# Swarm-Medusa-Antenna.net
KiCad netlist of a schematic drawn in Altium Designer
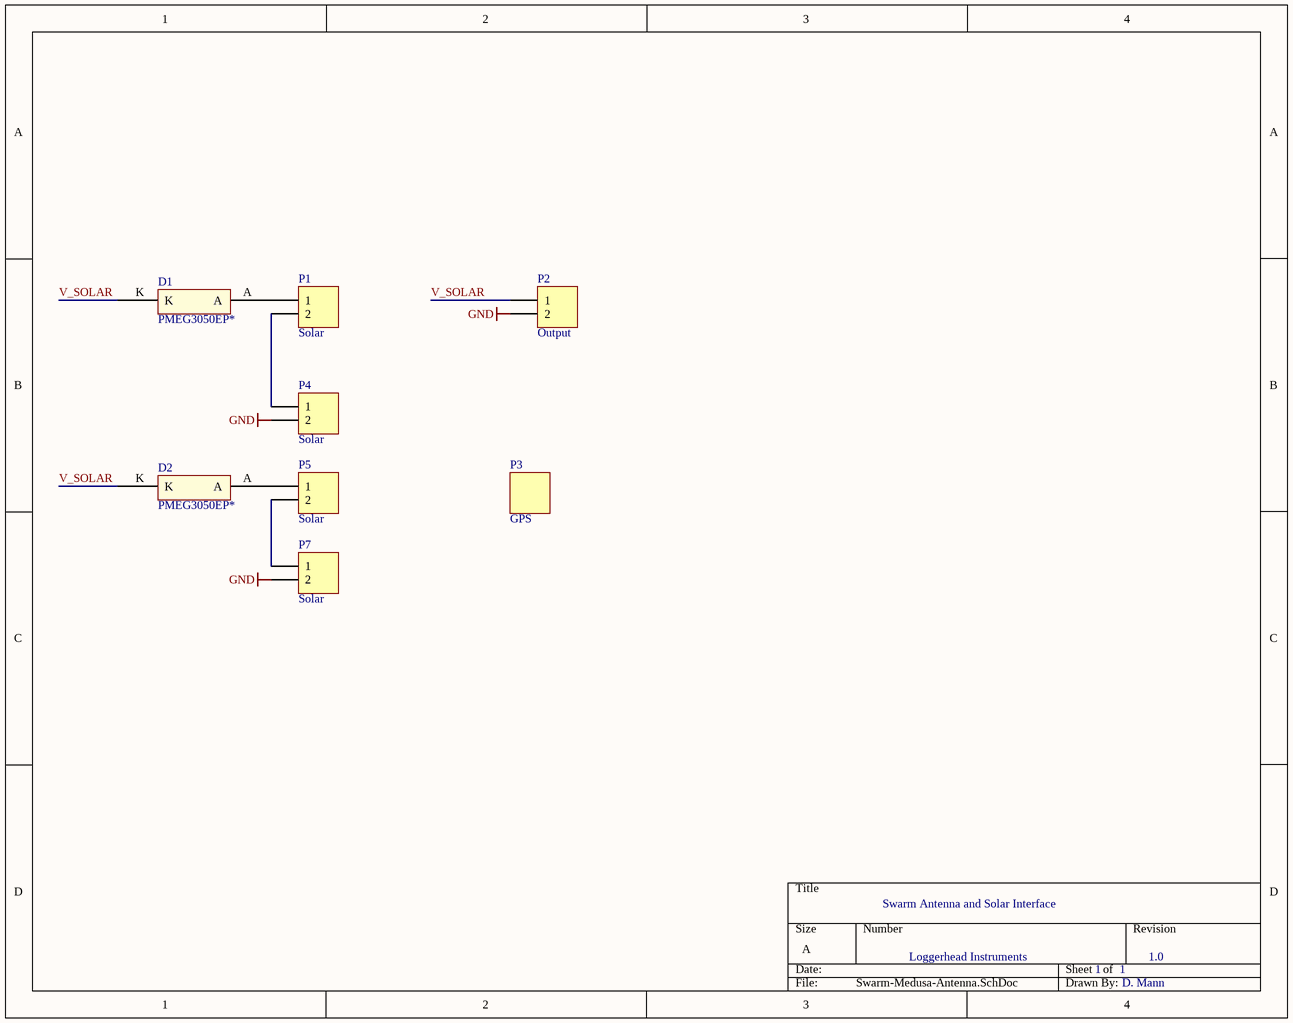
[diagram p0: Swarm-Medusa-Antenna.SchDoc]

(export (version "E")
  (design (tool "Eeschema 10.0.6"))
  (components
    (comp (ref "D1")
      (value "PMEG3050EP*")
      (footprint "Diode_PMEG3050EP")
      (libsource (lib "Loggerhead") (part "Diode_PMEG3050EP"))
    )
    (comp (ref "D2")
      (value "PMEG3050EP*")
      (footprint "Diode_PMEG3050EP")
      (libsource (lib "Loggerhead") (part "Diode_PMEG3050EP"))
    )
    (comp (ref "P1")
      (value "Solar")
      (footprint "HDR1X2")
      (description "Header, 2-Pin")
      (fields (field (name "PUBLISHER") "Altium Limited"))
      (libsource (lib "Miscellaneous Connectors") (part "Header 2"))
    )
    (comp (ref "P2")
      (value "Output")
      (footprint "HDR1X2")
      (description "Header, 2-Pin")
      (fields (field (name "PUBLISHER") "Altium Limited"))
      (libsource (lib "Miscellaneous Connectors") (part "Header 2"))
    )
    (comp (ref "P3")
      (value "GPS")
      (footprint "Iridium Antenna")
      (libsource (lib "Loggerhead") (part "Iridium Antenna"))
    )
    (comp (ref "P4")
      (value "Solar")
      (footprint "HDR1X2")
      (description "Header, 2-Pin")
      (fields (field (name "PUBLISHER") "Altium Limited"))
      (libsource (lib "Miscellaneous Connectors") (part "Header 2"))
    )
    (comp (ref "P5")
      (value "Solar")
      (footprint "HDR1X2")
      (description "Header, 2-Pin")
      (fields (field (name "PUBLISHER") "Altium Limited"))
      (libsource (lib "Miscellaneous Connectors") (part "Header 2"))
    )
    (comp (ref "P7")
      (value "Solar")
      (footprint "HDR1X2")
      (description "Header, 2-Pin")
      (fields (field (name "PUBLISHER") "Altium Limited"))
      (libsource (lib "Miscellaneous Connectors") (part "Header 2"))
    )
  )
  (nets
    (net (code "1") (name "/V_SOLAR") (class "Default")
      (node (ref "D1") (pin "K") (pinfunction "K_K") (pintype "passive"))
      (node (ref "D2") (pin "K") (pinfunction "K_K") (pintype "passive"))
      (node (ref "P2") (pin "1") (pinfunction "1_1") (pintype "passive"))
    )
    (net (code "2") (name "GND") (class "Default")
      (node (ref "P2") (pin "2") (pinfunction "2_2") (pintype "passive"))
      (node (ref "P4") (pin "2") (pinfunction "2_2") (pintype "passive"))
      (node (ref "P7") (pin "2") (pinfunction "2_2") (pintype "passive"))
    )
    (net (code "3") (name "Net-(D1-PadA)") (class "Default")
      (node (ref "D1") (pin "A") (pinfunction "A_A") (pintype "passive"))
      (node (ref "P1") (pin "1") (pinfunction "1_1") (pintype "passive"))
    )
    (net (code "4") (name "Net-(D2-PadA)") (class "Default")
      (node (ref "D2") (pin "A") (pinfunction "A_A") (pintype "passive"))
      (node (ref "P5") (pin "1") (pinfunction "1_1") (pintype "passive"))
    )
    (net (code "5") (name "Net-(P1-Pad2)") (class "Default")
      (node (ref "P1") (pin "2") (pinfunction "2_2") (pintype "passive"))
      (node (ref "P4") (pin "1") (pinfunction "1_1") (pintype "passive"))
    )
    (net (code "6") (name "Net-(P5-Pad2)") (class "Default")
      (node (ref "P5") (pin "2") (pinfunction "2_2") (pintype "passive"))
      (node (ref "P7") (pin "1") (pinfunction "1_1") (pintype "passive"))
    )
  )
)
